# Main.net
KiCad netlist of a schematic drawn in Altium Designer
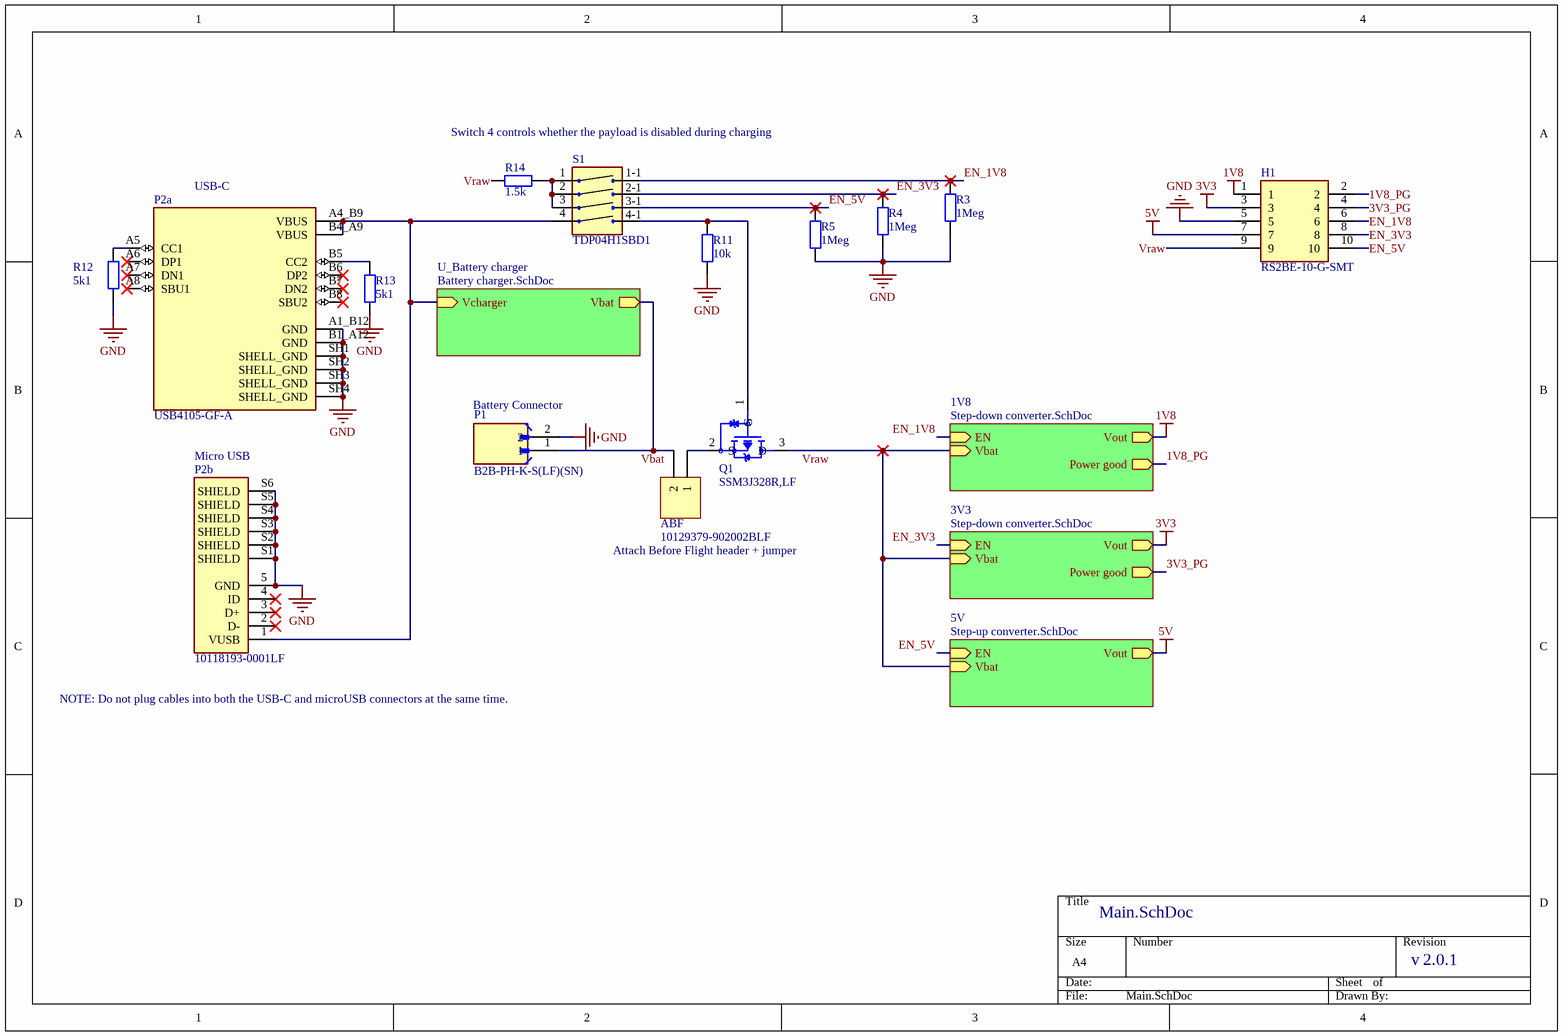
[diagram p0: Main.SchDoc]

(export (version "E")
  (design (tool "Eeschema 10.0.6"))
  (components
    (comp (ref "ABF")
      (value "10129379-902002BLF")
      (footprint "ECE-600102STTH-RA")
      (description "Short Before Flight")
      (libsource (lib "EceParts") (part "Header 2"))
    )
    (comp (ref "H1")
      (value "RS2BE-10-G-SMT")
      (footprint "RS2BE10GSMT")
      (description "Receptacle Strip 10P 2.54mm Pitch SMT")
      (libsource (lib "RS2BE-10-G-SMT") (part "RS2BE-10-G-SMT"))
    )
    (comp (ref "P1")
      (value "B2B-PH-K-S(LF)(SN)")
      (footprint "JST_B2B-PH-K-S(LF)(SN)")
      (description "Connector Header Through Hole 2 position 0.079 (2.00mm)")
      (fields (field (name "MF") "JST") (field (name "MP") "B2B-PH-K-S (LF)(SN)"))
      (libsource (lib "B2B-PH-K-S_LF__SN_") (part "B2B-PH-K-S(LF)(SN)"))
    )
    (comp (ref "P2a")
      (value "USB4105-GF-A")
      (footprint "GCT_USB4105-GF-A")
      (fields (field (name "MF") "GCT"))
      (libsource (lib "USB4105-GF-A") (part "USB4105-GF-A"))
    )
    (comp (ref "P2b")
      (value "10118193-0001LF")
      (footprint "AMPHENOL_10118193-0001LF")
      (description "Micro USB 2.0, Input Output Connectors, B TYPE RECEPTACLE")
      (fields (field (name "MF") "Amphenol ICC"))
      (libsource (lib "10118193-0001LF") (part "10118193-0001LF"))
    )
    (comp (ref "Q1")
      (value "SSM3J328R,LF")
      (footprint "SSMJ328R_LF:SOT95P240X88-3N")
      (description "P-Channel 20V 6A _Ta_ 1W _Ta_ Surface Mount SOT-23F")
      (fields (field (name "MF") "Toshiba"))
      (libsource (lib "SSMJ328R_LF") (part "SSM3J328R,LF"))
    )
    (comp (ref "R3")
      (value "1Meg")
      (footprint "0805")
      (description "Resistor")
      (libsource (lib "") (part "Res 0805_1"))
    )
    (comp (ref "R4")
      (value "1Meg")
      (footprint "0805")
      (description "Resistor")
      (libsource (lib "") (part "Res 0805_1"))
    )
    (comp (ref "R5")
      (value "1Meg")
      (footprint "0805")
      (description "Resistor")
      (libsource (lib "") (part "Res 0805_1"))
    )
    (comp (ref "R11")
      (value "10k")
      (footprint "0805")
      (description "Resistor")
      (libsource (lib "") (part "Res 0805_2"))
    )
    (comp (ref "R12")
      (value "5k1")
      (footprint "0805")
      (description "Resistor")
      (libsource (lib "") (part "Res 0805_1"))
    )
    (comp (ref "R13")
      (value "5k1")
      (footprint "0805")
      (description "Resistor")
      (libsource (lib "") (part "Res 0805_2"))
    )
    (comp (ref "R14")
      (value "1.5k")
      (footprint "0805")
      (description "Resistor")
      (libsource (lib "General Components") (part "Res 0805"))
    )
    (comp (ref "S1")
      (value "TDP04H1SBD1")
      (footprint "General Components:TDP04H1SBD1")
      (description "Switch")
      (fields (field (name "MOUSER PART NUMBER") "611-TDP04H1SBD1"))
      (libsource (lib "General Components") (part "TDP04H1SBD1"))
    )
  )
  (nets
    (net (code "1") (name "/1V8_PG") (class "Default")
      (node (ref "H1") (pin "2") (pinfunction "2_2") (pintype "passive"))
    )
    (net (code "2") (name "/3V3_PG") (class "Default")
      (node (ref "H1") (pin "4") (pinfunction "4_4") (pintype "passive"))
    )
    (net (code "3") (name "/EN_1V8") (class "Default")
      (node (ref "H1") (pin "6") (pinfunction "6_6") (pintype "passive"))
      (node (ref "R3") (pin "1") (pinfunction "1_1") (pintype "passive"))
      (node (ref "S1") (pin "8") (pinfunction "1-1_8") (pintype "passive"))
    )
    (net (code "4") (name "/EN_3V3") (class "Default")
      (node (ref "H1") (pin "8") (pinfunction "8_8") (pintype "passive"))
      (node (ref "R4") (pin "1") (pinfunction "1_1") (pintype "passive"))
      (node (ref "S1") (pin "7") (pinfunction "2-1_7") (pintype "passive"))
    )
    (net (code "5") (name "/EN_5V") (class "Default")
      (node (ref "H1") (pin "10") (pinfunction "10_10") (pintype "passive"))
      (node (ref "R5") (pin "1") (pinfunction "1_1") (pintype "passive"))
      (node (ref "S1") (pin "6") (pinfunction "3-1_6") (pintype "passive"))
    )
    (net (code "6") (name "/Vbat") (class "Default")
      (node (ref "ABF") (pin "2") (pinfunction "2_2") (pintype "passive"))
      (node (ref "P1") (pin "1") (pinfunction "1_1") (pintype "passive"))
    )
    (net (code "7") (name "/Vcharger") (class "Default")
      (node (ref "P2a") (pin "A4_B9") (pinfunction "VBUS_A4_B9") (pintype "power_in"))
      (node (ref "P2a") (pin "B4_A9") (pinfunction "VBUS_B4_A9") (pintype "power_in"))
      (node (ref "P2b") (pin "1") (pinfunction "VUSB_1") (pintype "passive"))
      (node (ref "S1") (pin "4") (pintype "passive"))
    )
    (net (code "8") (name "/Vraw") (class "Default")
      (node (ref "H1") (pin "9") (pinfunction "9_9") (pintype "passive"))
      (node (ref "Q1") (pin "3") (pinfunction "D_3") (pintype "passive"))
      (node (ref "R14") (pin "1") (pinfunction "1_1") (pintype "passive"))
    )
    (net (code "9") (name "1V8") (class "Default")
      (node (ref "H1") (pin "1") (pinfunction "1_1") (pintype "passive"))
    )
    (net (code "10") (name "3V3") (class "Default")
      (node (ref "H1") (pin "3") (pinfunction "3_3") (pintype "passive"))
    )
    (net (code "11") (name "5V") (class "Default")
      (node (ref "H1") (pin "7") (pinfunction "7_7") (pintype "passive"))
    )
    (net (code "12") (name "GND") (class "Default")
      (node (ref "H1") (pin "5") (pinfunction "5_5") (pintype "passive"))
      (node (ref "P1") (pin "2") (pinfunction "2_2") (pintype "passive"))
      (node (ref "P2a") (pin "A1_B12") (pinfunction "GND_A1_B12") (pintype "power_in"))
      (node (ref "P2a") (pin "B1_A12") (pinfunction "GND_B1_A12") (pintype "power_in"))
      (node (ref "P2a") (pin "SH1") (pinfunction "SHELL_GND_SH1") (pintype "power_in"))
      (node (ref "P2a") (pin "SH2") (pinfunction "SHELL_GND_SH2") (pintype "power_in"))
      (node (ref "P2a") (pin "SH3") (pinfunction "SHELL_GND_SH3") (pintype "power_in"))
      (node (ref "P2a") (pin "SH4") (pinfunction "SHELL_GND_SH4") (pintype "power_in"))
      (node (ref "P2b") (pin "5") (pinfunction "GND_5") (pintype "passive"))
      (node (ref "P2b") (pin "S1") (pinfunction "SHIELD_S1") (pintype "passive"))
      (node (ref "P2b") (pin "S2") (pinfunction "SHIELD_S2") (pintype "passive"))
      (node (ref "P2b") (pin "S3") (pinfunction "SHIELD_S3") (pintype "passive"))
      (node (ref "P2b") (pin "S4") (pinfunction "SHIELD_S4") (pintype "passive"))
      (node (ref "P2b") (pin "S5") (pinfunction "SHIELD_S5") (pintype "passive"))
      (node (ref "P2b") (pin "S6") (pinfunction "SHIELD_S6") (pintype "passive"))
      (node (ref "R11") (pin "1") (pinfunction "1_1") (pintype "passive"))
      (node (ref "R12") (pin "2") (pinfunction "2_2") (pintype "passive"))
      (node (ref "R13") (pin "1") (pinfunction "1_1") (pintype "passive"))
      (node (ref "R3") (pin "2") (pinfunction "2_2") (pintype "passive"))
      (node (ref "R4") (pin "2") (pinfunction "2_2") (pintype "passive"))
      (node (ref "R5") (pin "2") (pinfunction "2_2") (pintype "passive"))
    )
    (net (code "13") (name "Net-(P2a-CC1)") (class "Default")
      (node (ref "P2a") (pin "A5") (pinfunction "CC1_A5") (pintype "bidirectional"))
      (node (ref "R12") (pin "1") (pinfunction "1_1") (pintype "passive"))
    )
    (net (code "14") (name "Net-(P2a-CC2)") (class "Default")
      (node (ref "P2a") (pin "B5") (pinfunction "CC2_B5") (pintype "bidirectional"))
      (node (ref "R13") (pin "2") (pinfunction "2_2") (pintype "passive"))
    )
    (net (code "15") (name "Net-(Q1-G)") (class "Default")
      (node (ref "Q1") (pin "1") (pinfunction "G_1") (pintype "passive"))
      (node (ref "R11") (pin "2") (pinfunction "2_2") (pintype "passive"))
      (node (ref "S1") (pin "5") (pinfunction "4-1_5") (pintype "passive"))
    )
    (net (code "16") (name "Net-(Q1-S)") (class "Default")
      (node (ref "ABF") (pin "1") (pinfunction "1_1") (pintype "passive"))
      (node (ref "Q1") (pin "2") (pinfunction "S_2") (pintype "passive"))
    )
    (net (code "17") (name "Net-(R14-Pad2)") (class "Default")
      (node (ref "R14") (pin "2") (pinfunction "2_2") (pintype "passive"))
      (node (ref "S1") (pin "1") (pintype "passive"))
      (node (ref "S1") (pin "2") (pintype "passive"))
      (node (ref "S1") (pin "3") (pintype "passive"))
    )
    (net (code "18") (name "unconnected-(P2a-DN1-PadA7)") (class "Default")
      (node (ref "P2a") (pin "A7") (pinfunction "DN1_A7") (pintype "bidirectional+no_connect"))
    )
    (net (code "19") (name "unconnected-(P2a-DN2-PadB7)") (class "Default")
      (node (ref "P2a") (pin "B7") (pinfunction "DN2_B7") (pintype "bidirectional+no_connect"))
    )
    (net (code "20") (name "unconnected-(P2a-DP1-PadA6)") (class "Default")
      (node (ref "P2a") (pin "A6") (pinfunction "DP1_A6") (pintype "bidirectional+no_connect"))
    )
    (net (code "21") (name "unconnected-(P2a-DP2-PadB6)") (class "Default")
      (node (ref "P2a") (pin "B6") (pinfunction "DP2_B6") (pintype "bidirectional+no_connect"))
    )
    (net (code "22") (name "unconnected-(P2a-SBU1-PadA8)") (class "Default")
      (node (ref "P2a") (pin "A8") (pinfunction "SBU1_A8") (pintype "bidirectional+no_connect"))
    )
    (net (code "23") (name "unconnected-(P2a-SBU2-PadB8)") (class "Default")
      (node (ref "P2a") (pin "B8") (pinfunction "SBU2_B8") (pintype "bidirectional+no_connect"))
    )
    (net (code "24") (name "unconnected-(P2b-D+-Pad3)") (class "Default")
      (node (ref "P2b") (pin "3") (pinfunction "D+_3") (pintype "passive+no_connect"))
    )
    (net (code "25") (name "unconnected-(P2b-D--Pad2)") (class "Default")
      (node (ref "P2b") (pin "2") (pinfunction "D-_2") (pintype "passive+no_connect"))
    )
    (net (code "26") (name "unconnected-(P2b-ID-Pad4)") (class "Default")
      (node (ref "P2b") (pin "4") (pinfunction "ID_4") (pintype "passive+no_connect"))
    )
  )
)
